# SubPowersupply.net
KiCad netlist of a schematic drawn in Altium Designer
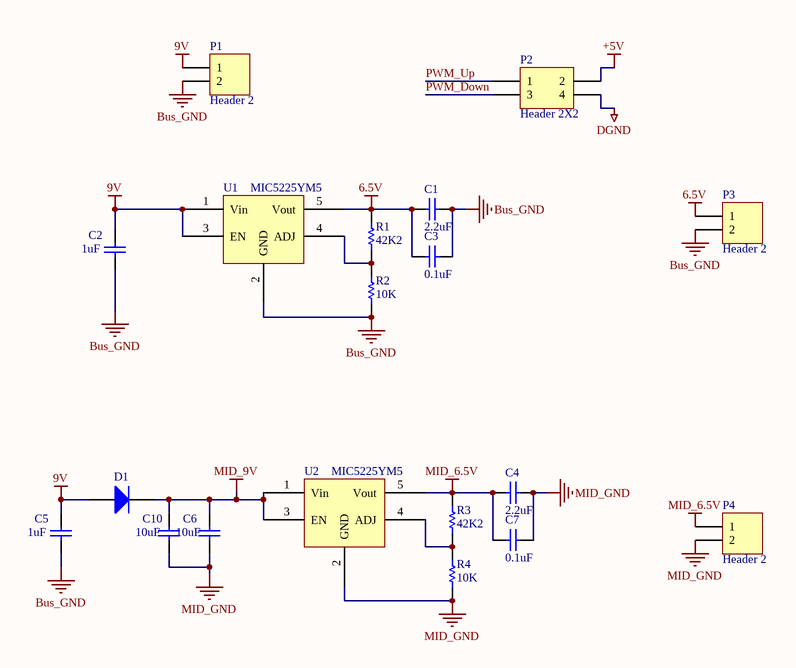
[diagram p0: SubPowersupply.SchDoc]

(export (version "E")
  (design (tool "Eeschema 10.0.6"))
  (components
    (comp (ref "C1")
      (value "2.2uF")
      (footprint "0603_C")
      (description "Capacitor")
      (fields
        (field (name "MANUFACTURER") "Generic Components")
        (field (name "PUBLISHER") "Altium Hobart Technology Centre")
      )
      (libsource (lib "Miscellaneous Devices") (part "Cap"))
    )
    (comp (ref "C2")
      (value "1uF")
      (footprint "0603_C")
      (description "Capacitor")
      (fields
        (field (name "MANUFACTURER") "Generic Components")
        (field (name "PUBLISHER") "Altium Hobart Technology Centre")
      )
      (libsource (lib "Miscellaneous Devices") (part "Cap"))
    )
    (comp (ref "C3")
      (value "0.1uF")
      (footprint "0603_C")
      (description "Capacitor")
      (fields
        (field (name "MANUFACTURER") "Generic Components")
        (field (name "PUBLISHER") "Altium Hobart Technology Centre")
      )
      (libsource (lib "Miscellaneous Devices") (part "Cap"))
    )
    (comp (ref "C4")
      (value "2.2uF")
      (footprint "0603_C")
      (description "Capacitor")
      (fields
        (field (name "MANUFACTURER") "Generic Components")
        (field (name "PUBLISHER") "Altium Hobart Technology Centre")
      )
      (libsource (lib "Miscellaneous Devices") (part "Cap"))
    )
    (comp (ref "C5")
      (value "1uF")
      (footprint "0603_C")
      (description "Capacitor")
      (fields
        (field (name "MANUFACTURER") "Generic Components")
        (field (name "PUBLISHER") "Altium Hobart Technology Centre")
      )
      (libsource (lib "Miscellaneous Devices") (part "Cap"))
    )
    (comp (ref "C6")
      (value "10uF")
      (footprint "0603_C")
      (description "Capacitor")
      (fields
        (field (name "MANUFACTURER") "Generic Components")
        (field (name "PUBLISHER") "Altium Hobart Technology Centre")
      )
      (libsource (lib "Miscellaneous Devices") (part "Cap"))
    )
    (comp (ref "C7")
      (value "0.1uF")
      (footprint "0603_C")
      (description "Capacitor")
      (fields
        (field (name "MANUFACTURER") "Generic Components")
        (field (name "PUBLISHER") "Altium Hobart Technology Centre")
      )
      (libsource (lib "Miscellaneous Devices") (part "Cap"))
    )
    (comp (ref "C10")
      (value "10uF")
      (footprint "0603_C")
      (description "Capacitor")
      (fields
        (field (name "MANUFACTURER") "Generic Components")
        (field (name "PUBLISHER") "Altium Hobart Technology Centre")
      )
      (libsource (lib "Miscellaneous Devices") (part "Cap"))
    )
    (comp (ref "D1")
      (value "Diode")
      (footprint "SMA")
      (description "Default Diode")
      (fields (field (name "PUBLISHER") "Altium Limited"))
      (libsource (lib "Miscellaneous Devices") (part "Diode"))
    )
    (comp (ref "P1")
      (value "Header 2")
      (footprint "HDR1X2")
      (description "Header, 2-Pin")
      (fields (field (name "PUBLISHER") "Altium Limited"))
      (libsource (lib "Miscellaneous Connectors") (part "Header 2"))
    )
    (comp (ref "P2")
      (value "Header 2X2")
      (footprint "HDR2X2")
      (description "Header, 2-Pin, Dual row")
      (fields (field (name "PUBLISHER") "Altium Limited"))
      (libsource (lib "Miscellaneous Connectors") (part "Header 2X2"))
    )
    (comp (ref "P3")
      (value "Header 2")
      (footprint "HDR1X2")
      (description "Header, 2-Pin")
      (fields (field (name "PUBLISHER") "Altium Limited"))
      (libsource (lib "Miscellaneous Connectors") (part "Header 2"))
    )
    (comp (ref "P4")
      (value "Header 2")
      (footprint "HDR1X2")
      (description "Header, 2-Pin")
      (fields (field (name "PUBLISHER") "Altium Limited"))
      (libsource (lib "Miscellaneous Connectors") (part "Header 2"))
    )
    (comp (ref "R1")
      (value "42K2")
      (footprint "0603_R")
      (description "Semiconductor Resistor")
      (fields (field (name "PUBLISHER") "Altium Limited"))
      (libsource (lib "Miscellaneous Devices") (part "Res Semi"))
    )
    (comp (ref "R2")
      (value "10K")
      (footprint "0603_R")
      (description "Semiconductor Resistor")
      (fields (field (name "PUBLISHER") "Altium Limited"))
      (libsource (lib "Miscellaneous Devices") (part "Res Semi"))
    )
    (comp (ref "R3")
      (value "42K2")
      (footprint "0603_R")
      (description "Semiconductor Resistor")
      (fields (field (name "PUBLISHER") "Altium Limited"))
      (libsource (lib "Miscellaneous Devices") (part "Res Semi"))
    )
    (comp (ref "R4")
      (value "10K")
      (footprint "0603_R")
      (description "Semiconductor Resistor")
      (fields (field (name "PUBLISHER") "Altium Limited"))
      (libsource (lib "Miscellaneous Devices") (part "Res Semi"))
    )
    (comp (ref "U1")
      (value "MIC5225YM5")
      (footprint "SOT23-5")
      (libsource (lib "Schlib_LZW") (part "MIC5225YM5"))
    )
    (comp (ref "U2")
      (value "MIC5225YM5")
      (footprint "SOT23-5")
      (libsource (lib "Schlib_LZW") (part "MIC5225YM5"))
    )
  )
  (nets
    (net (code "1") (name "+5V") (class "Default")
      (node (ref "P2") (pin "2") (pinfunction "2_2") (pintype "passive"))
    )
    (net (code "2") (name "/PWM_Down") (class "Default")
      (node (ref "P2") (pin "3") (pinfunction "3_3") (pintype "passive"))
    )
    (net (code "3") (name "/PWM_Up") (class "Default")
      (node (ref "P2") (pin "1") (pinfunction "1_1") (pintype "passive"))
    )
    (net (code "4") (name "6.5V") (class "Default")
      (node (ref "C1") (pin "2") (pinfunction "2_2") (pintype "passive"))
      (node (ref "C3") (pin "2") (pinfunction "2_2") (pintype "passive"))
      (node (ref "P3") (pin "1") (pinfunction "1_1") (pintype "passive"))
      (node (ref "R1") (pin "2") (pinfunction "2_2") (pintype "passive"))
      (node (ref "U1") (pin "5") (pinfunction "Vout_5") (pintype "passive"))
    )
    (net (code "5") (name "9V") (class "Default")
      (node (ref "C2") (pin "2") (pinfunction "2_2") (pintype "passive"))
      (node (ref "C5") (pin "2") (pinfunction "2_2") (pintype "passive"))
      (node (ref "D1") (pin "1") (pinfunction "A_1") (pintype "passive"))
      (node (ref "P1") (pin "1") (pinfunction "1_1") (pintype "passive"))
      (node (ref "U1") (pin "1") (pinfunction "Vin_1") (pintype "passive"))
      (node (ref "U1") (pin "3") (pinfunction "EN_3") (pintype "passive"))
    )
    (net (code "6") (name "Bus_GND") (class "Default")
      (node (ref "C1") (pin "1") (pinfunction "1_1") (pintype "passive"))
      (node (ref "C2") (pin "1") (pinfunction "1_1") (pintype "passive"))
      (node (ref "C3") (pin "1") (pinfunction "1_1") (pintype "passive"))
      (node (ref "C5") (pin "1") (pinfunction "1_1") (pintype "passive"))
      (node (ref "P1") (pin "2") (pinfunction "2_2") (pintype "passive"))
      (node (ref "P3") (pin "2") (pinfunction "2_2") (pintype "passive"))
      (node (ref "R2") (pin "1") (pinfunction "1_1") (pintype "passive"))
      (node (ref "U1") (pin "2") (pinfunction "GND_2") (pintype "passive"))
    )
    (net (code "7") (name "DGND") (class "Default")
      (node (ref "P2") (pin "4") (pinfunction "4_4") (pintype "passive"))
    )
    (net (code "8") (name "MID_6.5V") (class "Default")
      (node (ref "C4") (pin "2") (pinfunction "2_2") (pintype "passive"))
      (node (ref "C7") (pin "2") (pinfunction "2_2") (pintype "passive"))
      (node (ref "P4") (pin "1") (pinfunction "1_1") (pintype "passive"))
      (node (ref "R3") (pin "2") (pinfunction "2_2") (pintype "passive"))
      (node (ref "U2") (pin "5") (pinfunction "Vout_5") (pintype "passive"))
    )
    (net (code "9") (name "MID_9V") (class "Default")
      (node (ref "C10") (pin "2") (pinfunction "2_2") (pintype "passive"))
      (node (ref "C6") (pin "2") (pinfunction "2_2") (pintype "passive"))
      (node (ref "D1") (pin "2") (pinfunction "K_2") (pintype "passive"))
      (node (ref "U2") (pin "1") (pinfunction "Vin_1") (pintype "passive"))
      (node (ref "U2") (pin "3") (pinfunction "EN_3") (pintype "passive"))
    )
    (net (code "10") (name "MID_GND") (class "Default")
      (node (ref "C10") (pin "1") (pinfunction "1_1") (pintype "passive"))
      (node (ref "C4") (pin "1") (pinfunction "1_1") (pintype "passive"))
      (node (ref "C6") (pin "1") (pinfunction "1_1") (pintype "passive"))
      (node (ref "C7") (pin "1") (pinfunction "1_1") (pintype "passive"))
      (node (ref "P4") (pin "2") (pinfunction "2_2") (pintype "passive"))
      (node (ref "R4") (pin "1") (pinfunction "1_1") (pintype "passive"))
      (node (ref "U2") (pin "2") (pinfunction "GND_2") (pintype "passive"))
    )
    (net (code "11") (name "Net-(U1-ADJ)") (class "Default")
      (node (ref "R1") (pin "1") (pinfunction "1_1") (pintype "passive"))
      (node (ref "R2") (pin "2") (pinfunction "2_2") (pintype "passive"))
      (node (ref "U1") (pin "4") (pinfunction "ADJ_4") (pintype "passive"))
    )
    (net (code "12") (name "Net-(U2-ADJ)") (class "Default")
      (node (ref "R3") (pin "1") (pinfunction "1_1") (pintype "passive"))
      (node (ref "R4") (pin "2") (pinfunction "2_2") (pintype "passive"))
      (node (ref "U2") (pin "4") (pinfunction "ADJ_4") (pintype "passive"))
    )
  )
)
